# 2_MicroController.net
KiCad netlist of a schematic drawn in Altium Designer
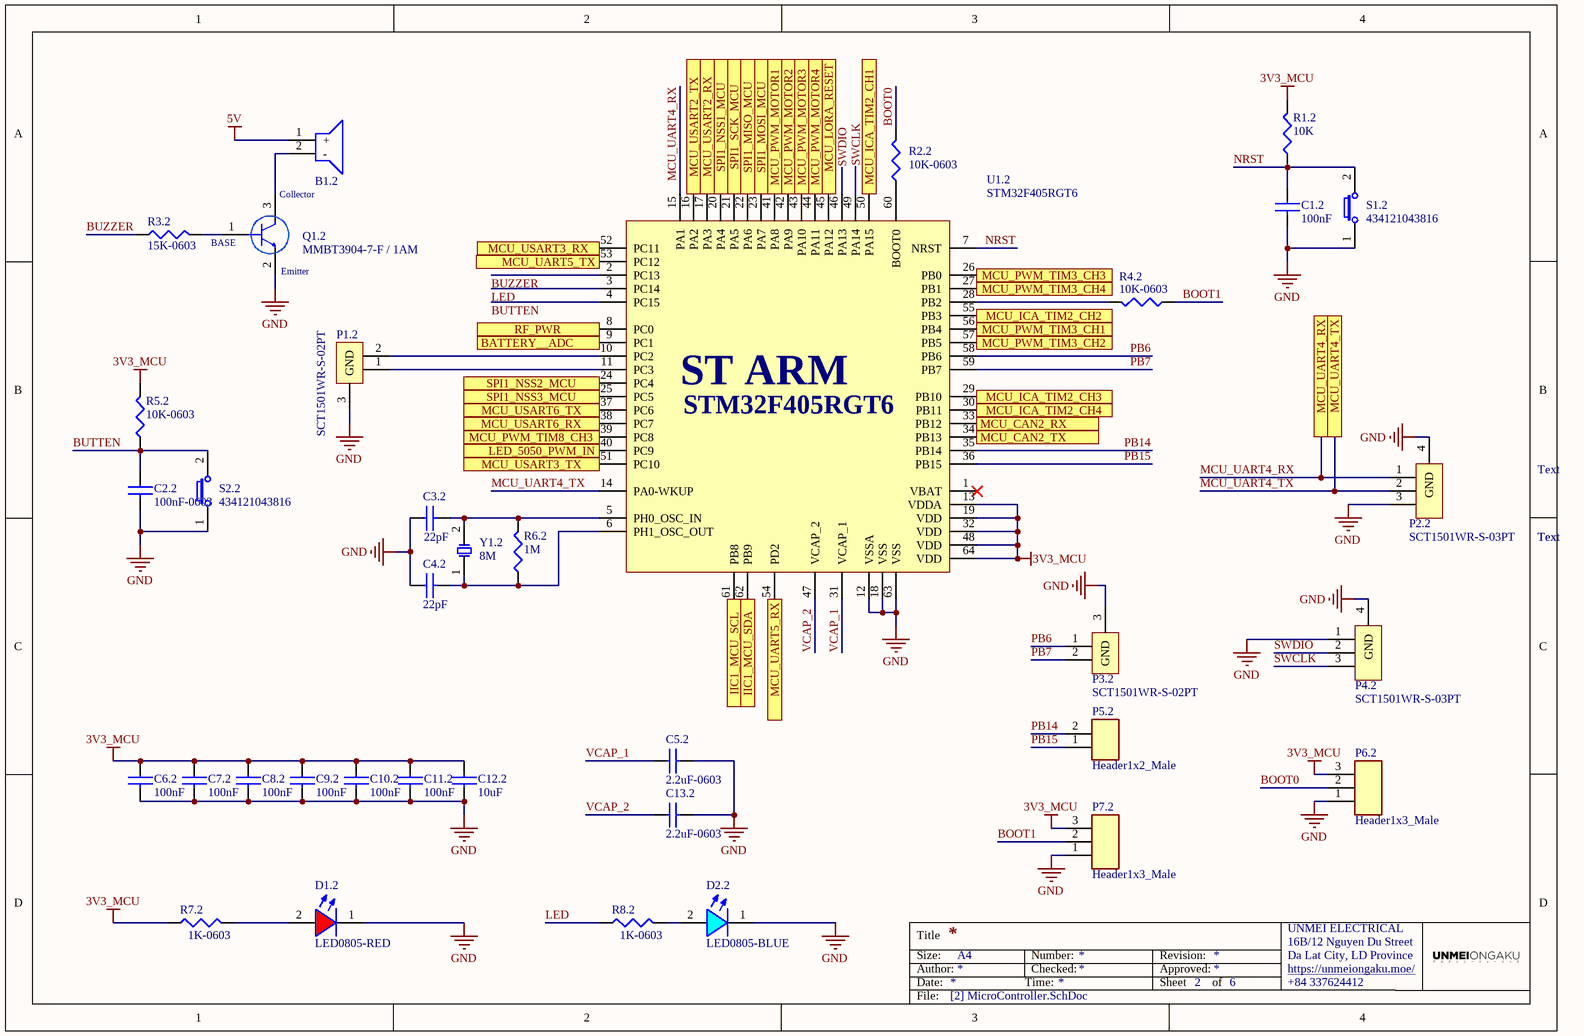
[diagram p0: [2] MicroController.SchDoc]

(export (version "E")
  (design (tool "Eeschema 10.0.6"))
  (components
    (comp (ref "B1.2")
      (value "Buzzer")
      (footprint "Buzzer 9x5mm 60dB")
      (description "9050 DIP Buzzer 9x5mm 60dB")
      (fields (field (name "LOCAL SUPPLIER PART NUMBER") "1209 DIP Buzzer 12x9mm"))
      (libsource (lib "Minh_Lib") (part "Buzzer 9050 - DIP"))
    )
    (comp (ref "C1.2")
      (value "100nF")
      (footprint "CAP0603")
      (description "CAP CER 0.1UF 50V X7R 0603")
      (fields (field (name "TOLERANCE") "±10%"))
      (libsource (lib "Minh_Lib") (part "CC0603KRX7R9BB104"))
    )
    (comp (ref "C2.2")
      (value "100nF-0603")
      (footprint "CAP0603")
      (description "CAP CER 0.1UF 50V X7R 0603")
      (fields (field (name "TOLERANCE") "±10%"))
      (libsource (lib "Minh_Lib") (part "CC0603KRX7R9BB104"))
    )
    (comp (ref "C3.2")
      (value "22pF")
      (footprint "CAP0603")
      (description "Surface Mount Ceramic Multilayer Capacitor 22pF 5% C0G 50V 0603 Paper T/R")
      (fields
        (field (name "MANUFACTURER") "Yageo")
        (field (name "MANUFACTURER PART NUMBER") "CC0603JRNPO9BN220")
      )
      (libsource (lib "Minh_Lib") (part "CC0603JRNPO9BN220"))
    )
    (comp (ref "C4.2")
      (value "22pF")
      (footprint "CAP0603")
      (description "Surface Mount Ceramic Multilayer Capacitor 22pF 5% C0G 50V 0603 Paper T/R")
      (fields
        (field (name "MANUFACTURER") "Yageo")
        (field (name "MANUFACTURER PART NUMBER") "CC0603JRNPO9BN220")
      )
      (libsource (lib "Minh_Lib") (part "CC0603JRNPO9BN220"))
    )
    (comp (ref "C5.2")
      (value "2.2uF-0603")
      (footprint "CAP0603")
      (description "CAP CER 2.2UF 10V X7R 0603")
      (fields (field (name "TOLERANCE") "±10%"))
      (libsource (lib "Minh_Lib") (part "CC0603KRX7R6BB225"))
    )
    (comp (ref "C6.2")
      (value "100nF")
      (footprint "CAP0603")
      (description "CAP CER 0.1UF 50V X7R 0603")
      (fields (field (name "TOLERANCE") "±10%"))
      (libsource (lib "Minh_Lib") (part "CC0603KRX7R9BB104"))
    )
    (comp (ref "C7.2")
      (value "100nF")
      (footprint "CAP0603")
      (description "CAP CER 0.1UF 50V X7R 0603")
      (fields (field (name "TOLERANCE") "±10%"))
      (libsource (lib "Minh_Lib") (part "CC0603KRX7R9BB104"))
    )
    (comp (ref "C8.2")
      (value "100nF")
      (footprint "CAP0603")
      (description "CAP CER 0.1UF 50V X7R 0603")
      (fields (field (name "TOLERANCE") "±10%"))
      (libsource (lib "Minh_Lib") (part "CC0603KRX7R9BB104"))
    )
    (comp (ref "C9.2")
      (value "100nF")
      (footprint "CAP0603")
      (description "CAP CER 0.1UF 50V X7R 0603")
      (fields (field (name "TOLERANCE") "±10%"))
      (libsource (lib "Minh_Lib") (part "CC0603KRX7R9BB104"))
    )
    (comp (ref "C10.2")
      (value "100nF")
      (footprint "CAP0603")
      (description "CAP CER 0.1UF 50V X7R 0603")
      (fields (field (name "TOLERANCE") "±10%"))
      (libsource (lib "Minh_Lib") (part "CC0603KRX7R9BB104"))
    )
    (comp (ref "C11.2")
      (value "100nF")
      (footprint "CAP0603")
      (description "CAP CER 0.1UF 50V X7R 0603")
      (fields (field (name "TOLERANCE") "±10%"))
      (libsource (lib "Minh_Lib") (part "CC0603KRX7R9BB104"))
    )
    (comp (ref "C12.2")
      (value "10uF")
      (footprint "CAP0603")
      (description "CAP CER 10UF 10V X5R 0603")
      (fields (field (name "TOLERANCE") "±10%"))
      (libsource (lib "Minh_Lib") (part "CC0603KRX5R6BB106"))
    )
    (comp (ref "C13.2")
      (value "2.2uF-0603")
      (footprint "CAP0603")
      (description "CAP CER 2.2UF 10V X7R 0603")
      (fields (field (name "TOLERANCE") "±10%"))
      (libsource (lib "Minh_Lib") (part "CC0603KRX7R6BB225"))
    )
    (comp (ref "D1.2")
      (value "LED0805-RED")
      (footprint "LED0805-RED")
      (libsource (lib "Minh_Lib") (part "LED0805-RED"))
    )
    (comp (ref "D2.2")
      (value "LED0805-BLUE")
      (footprint "LED0805-BLUE")
      (libsource (lib "Minh_Lib") (part "LED0805-BLUE"))
    )
    (comp (ref "P1.2")
      (value "SCT1501WR-S-02PT")
      (footprint "Connector ZH1.5 2P SMD")
      (libsource (lib "Minh_Lib") (part "SCT1501WR-S-02PT"))
    )
    (comp (ref "P2.2")
      (value "SCT1501WR-S-03PT")
      (footprint "Connector ZH1.5 3P SMD")
      (libsource (lib "Minh_Lib") (part "SCT1501WR-S-03PT"))
    )
    (comp (ref "P3.2")
      (value "SCT1501WR-S-02PT")
      (footprint "Connector ZH1.5 2P SMD")
      (libsource (lib "") (part "SCT1501WR-S-02PT_1"))
    )
    (comp (ref "P4.2")
      (value "SCT1501WR-S-03PT")
      (footprint "Connector ZH1.5 3P SMD")
      (libsource (lib "Minh_Lib") (part "SCT1501WR-S-03PT"))
    )
    (comp (ref "P5.2")
      (value "Header1x2_Male")
      (footprint "Minh_Lib:HDR1x2_2.54_MALE")
      (description "Header1x2_2.54_MALE")
      (libsource (lib "Minh_Lib") (part "HDR1x2_2.54_MALE"))
    )
    (comp (ref "P6.2")
      (value "Header1x3_Male")
      (footprint "Minh_Lib:HDR1x3_2.54_MALE")
      (description "Header1x3_2.54_MALE")
      (libsource (lib "Minh_Lib") (part "HDR1x3_2.54_MALE"))
    )
    (comp (ref "P7.2")
      (value "Header1x3_Male")
      (footprint "Minh_Lib:HDR1x3_2.54_MALE")
      (description "Header1x3_2.54_MALE")
      (libsource (lib "Minh_Lib") (part "HDR1x3_2.54_MALE"))
    )
    (comp (ref "Q1.2")
      (value "MMBT3904-7-F / 1AM")
      (footprint "SOT23")
      (description "Transistor General Purpose BJT NPN 40 Volt 0.2A Automotive 3-Pin SOT-23")
      (fields
        (field (name "MANUFACTURER") "Diodes Zetex")
        (field (name "MANUFACTURER PART NUMBER") "MMBT3904-7-F")
      )
      (libsource (lib "Minh_Lib") (part "MMBT3904-7-F / 1AM"))
    )
    (comp (ref "R1.2")
      (value "10K")
      (footprint "RES0603 - 3D")
      (description "RES SMD 10K OHM 1% 1/10W 0603")
      (fields
        (field (name "MANUFACTURER") "Yageo")
        (field (name "MANUFACTURER PART NUMBER") "RC0603FR-0710KL")
      )
      (libsource (lib "Minh_Lib") (part "RC0603FR-0710KL"))
    )
    (comp (ref "R2.2")
      (value "10K-0603")
      (footprint "RES0603 - 3D")
      (description "RES SMD 10K OHM 1% 1/10W 0603")
      (fields
        (field (name "MANUFACTURER") "Yageo")
        (field (name "MANUFACTURER PART NUMBER") "RC0603FR-0710KL")
      )
      (libsource (lib "Minh_Lib") (part "RC0603FR-0710KL"))
    )
    (comp (ref "R3.2")
      (value "15K-0603")
      (footprint "RES0603 - 3D")
      (description "Thick Film Resistors - SMD 15K OHM 5%")
      (fields
        (field (name "MANUFACTURER") "Yageo")
        (field (name "MANUFACTURER PART NUMBER") "RC0603JR-0715KL")
      )
      (libsource (lib "Minh_Lib") (part "RC0603JR-0715KL"))
    )
    (comp (ref "R4.2")
      (value "10K-0603")
      (footprint "RES0603 - 3D")
      (description "RES SMD 10K OHM 1% 1/10W 0603")
      (fields
        (field (name "MANUFACTURER") "Yageo")
        (field (name "MANUFACTURER PART NUMBER") "RC0603FR-0710KL")
      )
      (libsource (lib "Minh_Lib") (part "RC0603FR-0710KL"))
    )
    (comp (ref "R5.2")
      (value "10K-0603")
      (footprint "RES0603 - 3D")
      (description "RES SMD 10K OHM 1% 1/10W 0603")
      (fields
        (field (name "MANUFACTURER") "Yageo")
        (field (name "MANUFACTURER PART NUMBER") "RC0603FR-0710KL")
      )
      (libsource (lib "Minh_Lib") (part "RC0603FR-0710KL"))
    )
    (comp (ref "R6.2")
      (value "1M")
      (footprint "RES0603 - 3D")
      (description "RES SMD 1M OHM 5% 1/10W 0603")
      (fields (field (name "TOLERANCE") "±5%"))
      (libsource (lib "Minh_Lib") (part "RC0603JR-071ML"))
    )
    (comp (ref "R7.2")
      (value "1K-0603")
      (footprint "RES0603 - 3D")
      (description "RES SMD 1K OHM 5% 1/10W 0603")
      (fields (field (name "TOLERANCE") "±5%"))
      (libsource (lib "Minh_Lib") (part "RC0603JR-071KL"))
    )
    (comp (ref "R8.2")
      (value "1K-0603")
      (footprint "RES0603 - 3D")
      (description "RES SMD 1K OHM 5% 1/10W 0603")
      (fields (field (name "TOLERANCE") "±5%"))
      (libsource (lib "Minh_Lib") (part "RC0603JR-071KL"))
    )
    (comp (ref "S1.2")
      (value "434121043816")
      (footprint "Switches-6x3.5x4.3mm")
      (description "Switch Tactile Spst-no 0.05A 12V")
      (fields (field (name "MANUFACTURER") "Wurth Electronics"))
      (libsource (lib "Minh_Lib") (part "434121043816"))
    )
    (comp (ref "S2.2")
      (value "434121043816")
      (footprint "Switches-6x3.5x4.3mm")
      (description "Switch Tactile Spst-no 0.05A 12V")
      (fields (field (name "MANUFACTURER") "Wurth Electronics"))
      (libsource (lib "Minh_Lib") (part "434121043816"))
    )
    (comp (ref "U1.2")
      (value "STM32F405RGT6")
      (footprint "LQFP64")
      (description "IC MCU 32BIT 1MB FLASH 64LQFP")
      (fields (field (name "MANUFACTURER") "STMicroelectronics"))
      (libsource (lib "Minh_Lib") (part "STM32F405RGT6"))
    )
    (comp (ref "Y1.2")
      (value "8M")
      (footprint "HC49-S")
      (description "Crystals LO-PRO 8MHz")
      (fields
        (field (name "MANUFACTURER") "Fox Electronics")
        (field (name "MANUFACTURER PART NUMBER") "HC49SSDLF-8.00MHz")
      )
      (libsource (lib "Minh_Lib") (part "Crystals - HC49SSDLF-8.00MHz"))
    )
  )
  (nets
    (net (code "1") (name "/BATTERY__ADC") (class "Default")
      (node (ref "U1.2") (pin "9") (pinfunction "PC1_9") (pintype "passive"))
    )
    (net (code "2") (name "/BOOT0") (class "Default")
      (node (ref "P6.2") (pin "2") (pinfunction "2_2") (pintype "passive"))
      (node (ref "R2.2") (pin "2") (pinfunction "2_2") (pintype "passive"))
    )
    (net (code "3") (name "/BOOT1") (class "Default")
      (node (ref "P7.2") (pin "2") (pinfunction "2_2") (pintype "passive"))
      (node (ref "R4.2") (pin "1") (pinfunction "1_1") (pintype "passive"))
    )
    (net (code "4") (name "/BUTTEN") (class "Default")
      (node (ref "C2.2") (pin "1") (pinfunction "1_1") (pintype "passive"))
      (node (ref "R5.2") (pin "1") (pinfunction "1_1") (pintype "passive"))
      (node (ref "S2.2") (pin "2") (pinfunction "2_2") (pintype "passive"))
      (node (ref "U1.2") (pin "4") (pinfunction "PC15_4") (pintype "passive"))
    )
    (net (code "5") (name "/BUZZER") (class "Default")
      (node (ref "R3.2") (pin "1") (pinfunction "1_1") (pintype "passive"))
      (node (ref "U1.2") (pin "2") (pinfunction "PC13_2") (pintype "passive"))
    )
    (net (code "6") (name "/IIC1_MCU_SCL") (class "Default")
      (node (ref "U1.2") (pin "61") (pinfunction "PB8_61") (pintype "passive"))
    )
    (net (code "7") (name "/IIC1_MCU_SDA") (class "Default")
      (node (ref "U1.2") (pin "62") (pinfunction "PB9_62") (pintype "passive"))
    )
    (net (code "8") (name "/LED") (class "Default")
      (node (ref "R8.2") (pin "1") (pinfunction "1_1") (pintype "passive"))
      (node (ref "U1.2") (pin "3") (pinfunction "PC14_3") (pintype "passive"))
    )
    (net (code "9") (name "/LED_5050_PWM_IN") (class "Default")
      (node (ref "U1.2") (pin "40") (pinfunction "PC9_40") (pintype "passive"))
    )
    (net (code "25") (name "/MCU_PWM_TIM8_CH3") (class "Default")
      (node (ref "U1.2") (pin "39") (pinfunction "PC8_39") (pintype "passive"))
    )
    (net (code "26") (name "/MCU_UART4_RX") (class "Default")
      (node (ref "P2.2") (pin "1") (pinfunction "1_1") (pintype "passive"))
      (node (ref "U1.2") (pin "15") (pinfunction "PA1_15") (pintype "passive"))
    )
    (net (code "27") (name "/MCU_UART4_TX") (class "Default")
      (node (ref "P2.2") (pin "2") (pinfunction "2_2") (pintype "passive"))
      (node (ref "U1.2") (pin "14") (pinfunction "PA0-WKUP_14") (pintype "passive"))
    )
    (net (code "28") (name "/MCU_UART5_RX") (class "Default")
      (node (ref "U1.2") (pin "54") (pinfunction "PD2_54") (pintype "passive"))
    )
    (net (code "29") (name "/MCU_UART5_TX") (class "Default")
      (node (ref "U1.2") (pin "53") (pinfunction "PC12_53") (pintype "passive"))
    )
    (net (code "32") (name "/MCU_USART3_RX") (class "Default")
      (node (ref "U1.2") (pin "52") (pinfunction "PC11_52") (pintype "passive"))
    )
    (net (code "33") (name "/MCU_USART3_TX") (class "Default")
      (node (ref "U1.2") (pin "51") (pinfunction "PC10_51") (pintype "passive"))
    )
    (net (code "34") (name "/MCU_USART6_RX") (class "Default")
      (node (ref "U1.2") (pin "38") (pinfunction "PC7_38") (pintype "passive"))
    )
    (net (code "35") (name "/MCU_USART6_TX") (class "Default")
      (node (ref "U1.2") (pin "37") (pinfunction "PC6_37") (pintype "passive"))
    )
    (net (code "36") (name "/NRST") (class "Default")
      (node (ref "C1.2") (pin "1") (pinfunction "1_1") (pintype "passive"))
      (node (ref "R1.2") (pin "1") (pinfunction "1_1") (pintype "passive"))
      (node (ref "S1.2") (pin "2") (pinfunction "2_2") (pintype "passive"))
      (node (ref "U1.2") (pin "7") (pinfunction "NRST_7") (pintype "passive"))
    )
    (net (code "37") (name "/PB6") (class "Default")
      (node (ref "P3.2") (pin "1") (pinfunction "1_1") (pintype "passive"))
      (node (ref "U1.2") (pin "58") (pinfunction "PB6_58") (pintype "passive"))
    )
    (net (code "38") (name "/PB7") (class "Default")
      (node (ref "P3.2") (pin "2") (pinfunction "2_2") (pintype "passive"))
      (node (ref "U1.2") (pin "59") (pinfunction "PB7_59") (pintype "passive"))
    )
    (net (code "39") (name "/PB14") (class "Default")
      (node (ref "P5.2") (pin "2") (pinfunction "2_2") (pintype "passive"))
      (node (ref "U1.2") (pin "35") (pinfunction "PB14_35") (pintype "passive"))
    )
    (net (code "40") (name "/PB15") (class "Default")
      (node (ref "P5.2") (pin "1") (pinfunction "1_1") (pintype "passive"))
      (node (ref "U1.2") (pin "36") (pinfunction "PB15_36") (pintype "passive"))
    )
    (net (code "41") (name "/RF_PWR") (class "Default")
      (node (ref "U1.2") (pin "8") (pinfunction "PC0_8") (pintype "passive"))
    )
    (net (code "45") (name "/SPI1_NSS2_MCU") (class "Default")
      (node (ref "U1.2") (pin "24") (pinfunction "PC4_24") (pintype "passive"))
    )
    (net (code "46") (name "/SPI1_NSS3_MCU") (class "Default")
      (node (ref "U1.2") (pin "25") (pinfunction "PC5_25") (pintype "passive"))
    )
    (net (code "48") (name "/SWCLK") (class "Default")
      (node (ref "P4.2") (pin "3") (pinfunction "3_3") (pintype "passive"))
      (node (ref "U1.2") (pin "49") (pinfunction "PA14_49") (pintype "passive"))
    )
    (net (code "49") (name "/SWDIO") (class "Default")
      (node (ref "P4.2") (pin "2") (pinfunction "2_2") (pintype "passive"))
      (node (ref "U1.2") (pin "46") (pinfunction "PA13_46") (pintype "passive"))
    )
    (net (code "50") (name "/VCAP_1") (class "Default")
      (node (ref "C5.2") (pin "1") (pinfunction "1_1") (pintype "passive"))
      (node (ref "U1.2") (pin "31") (pinfunction "VCAP_1_31") (pintype "passive"))
    )
    (net (code "51") (name "/VCAP_2") (class "Default")
      (node (ref "C13.2") (pin "1") (pinfunction "1_1") (pintype "passive"))
      (node (ref "U1.2") (pin "47") (pinfunction "VCAP_2_47") (pintype "passive"))
    )
    (net (code "52") (name "3V3_MCU") (class "Default")
      (node (ref "C10.2") (pin "1") (pinfunction "1_1") (pintype "passive"))
      (node (ref "C11.2") (pin "1") (pinfunction "1_1") (pintype "passive"))
      (node (ref "C12.2") (pin "1") (pinfunction "1_1") (pintype "passive"))
      (node (ref "C6.2") (pin "1") (pinfunction "1_1") (pintype "passive"))
      (node (ref "C7.2") (pin "1") (pinfunction "1_1") (pintype "passive"))
      (node (ref "C8.2") (pin "1") (pinfunction "1_1") (pintype "passive"))
      (node (ref "C9.2") (pin "1") (pinfunction "1_1") (pintype "passive"))
      (node (ref "P6.2") (pin "3") (pinfunction "3_3") (pintype "passive"))
      (node (ref "P7.2") (pin "3") (pinfunction "3_3") (pintype "passive"))
      (node (ref "R1.2") (pin "2") (pinfunction "2_2") (pintype "passive"))
      (node (ref "R5.2") (pin "2") (pinfunction "2_2") (pintype "passive"))
      (node (ref "R7.2") (pin "1") (pinfunction "1_1") (pintype "passive"))
      (node (ref "U1.2") (pin "13") (pinfunction "VDDA_13") (pintype "passive"))
      (node (ref "U1.2") (pin "19") (pinfunction "VDD_19") (pintype "passive"))
      (node (ref "U1.2") (pin "32") (pinfunction "VDD_32") (pintype "passive"))
      (node (ref "U1.2") (pin "48") (pinfunction "VDD_48") (pintype "passive"))
      (node (ref "U1.2") (pin "64") (pinfunction "VDD_64") (pintype "passive"))
    )
    (net (code "53") (name "5V") (class "Default")
      (node (ref "B1.2") (pin "1") (pinfunction "+_1") (pintype "passive"))
    )
    (net (code "54") (name "GND") (class "Default")
      (node (ref "C1.2") (pin "2") (pinfunction "2_2") (pintype "passive"))
      (node (ref "C10.2") (pin "2") (pinfunction "2_2") (pintype "passive"))
      (node (ref "C11.2") (pin "2") (pinfunction "2_2") (pintype "passive"))
      (node (ref "C12.2") (pin "2") (pinfunction "2_2") (pintype "passive"))
      (node (ref "C13.2") (pin "2") (pinfunction "2_2") (pintype "passive"))
      (node (ref "C2.2") (pin "2") (pinfunction "2_2") (pintype "passive"))
      (node (ref "C3.2") (pin "1") (pinfunction "1_1") (pintype "passive"))
      (node (ref "C4.2") (pin "1") (pinfunction "1_1") (pintype "passive"))
      (node (ref "C5.2") (pin "2") (pinfunction "2_2") (pintype "passive"))
      (node (ref "C6.2") (pin "2") (pinfunction "2_2") (pintype "passive"))
      (node (ref "C7.2") (pin "2") (pinfunction "2_2") (pintype "passive"))
      (node (ref "C8.2") (pin "2") (pinfunction "2_2") (pintype "passive"))
      (node (ref "C9.2") (pin "2") (pinfunction "2_2") (pintype "passive"))
      (node (ref "D1.2") (pin "1") (pinfunction "+_1") (pintype "passive"))
      (node (ref "D2.2") (pin "1") (pinfunction "+_1") (pintype "passive"))
      (node (ref "P1.2") (pin "3") (pinfunction "GND_3") (pintype "passive"))
      (node (ref "P2.2") (pin "3") (pinfunction "3_3") (pintype "passive"))
      (node (ref "P2.2") (pin "4") (pinfunction "GND_4") (pintype "passive"))
      (node (ref "P3.2") (pin "3") (pinfunction "GND_3") (pintype "passive"))
      (node (ref "P4.2") (pin "1") (pinfunction "1_1") (pintype "passive"))
      (node (ref "P4.2") (pin "4") (pinfunction "GND_4") (pintype "passive"))
      (node (ref "P6.2") (pin "1") (pinfunction "1_1") (pintype "passive"))
      (node (ref "P7.2") (pin "1") (pinfunction "1_1") (pintype "passive"))
      (node (ref "Q1.2") (pin "2") (pinfunction "2_2") (pintype "passive"))
      (node (ref "S1.2") (pin "1") (pinfunction "1_1") (pintype "passive"))
      (node (ref "S2.2") (pin "1") (pinfunction "1_1") (pintype "passive"))
      (node (ref "U1.2") (pin "12") (pinfunction "VSSA_12") (pintype "passive"))
      (node (ref "U1.2") (pin "18") (pinfunction "VSS_18") (pintype "passive"))
      (node (ref "U1.2") (pin "63") (pinfunction "VSS_63") (pintype "passive"))
    )
    (net (code "55") (name "Net-(B1.2--)") (class "Default")
      (node (ref "B1.2") (pin "2") (pinfunction "-_2") (pintype "passive"))
      (node (ref "Q1.2") (pin "3") (pinfunction "3_3") (pintype "passive"))
    )
    (net (code "56") (name "Net-(D1.2-+-Pad2)") (class "Default")
      (node (ref "D1.2") (pin "2") (pinfunction "+_2") (pintype "passive"))
      (node (ref "R7.2") (pin "2") (pinfunction "2_2") (pintype "passive"))
    )
    (net (code "57") (name "Net-(D2.2-+-Pad2)") (class "Default")
      (node (ref "D2.2") (pin "2") (pinfunction "+_2") (pintype "passive"))
      (node (ref "R8.2") (pin "2") (pinfunction "2_2") (pintype "passive"))
    )
    (net (code "58") (name "Net-(Q1.2-Pad1)") (class "Default")
      (node (ref "Q1.2") (pin "1") (pinfunction "1_1") (pintype "passive"))
      (node (ref "R3.2") (pin "2") (pinfunction "2_2") (pintype "passive"))
    )
    (net (code "59") (name "Net-(U1.2-BOOT0)") (class "Default")
      (node (ref "R2.2") (pin "1") (pinfunction "1_1") (pintype "passive"))
      (node (ref "U1.2") (pin "60") (pinfunction "BOOT0_60") (pintype "passive"))
    )
    (net (code "60") (name "Net-(U1.2-PB2)") (class "Default")
      (node (ref "R4.2") (pin "2") (pinfunction "2_2") (pintype "passive"))
      (node (ref "U1.2") (pin "28") (pinfunction "PB2_28") (pintype "passive"))
    )
    (net (code "61") (name "Net-(U1.2-PC2)") (class "Default")
      (node (ref "P1.2") (pin "2") (pinfunction "2_2") (pintype "passive"))
      (node (ref "U1.2") (pin "10") (pinfunction "PC2_10") (pintype "passive"))
    )
    (net (code "62") (name "Net-(U1.2-PC3)") (class "Default")
      (node (ref "P1.2") (pin "1") (pinfunction "1_1") (pintype "passive"))
      (node (ref "U1.2") (pin "11") (pinfunction "PC3_11") (pintype "passive"))
    )
    (net (code "63") (name "Net-(U1.2-PH0_OSC_IN)") (class "Default")
      (node (ref "C3.2") (pin "2") (pinfunction "2_2") (pintype "passive"))
      (node (ref "R6.2") (pin "2") (pinfunction "2_2") (pintype "passive"))
      (node (ref "U1.2") (pin "5") (pinfunction "PH0_OSC_IN_5") (pintype "passive"))
      (node (ref "Y1.2") (pin "2") (pinfunction "7_2") (pintype "passive"))
    )
    (net (code "64") (name "Net-(U1.2-PH1_OSC_OUT)") (class "Default")
      (node (ref "C4.2") (pin "2") (pinfunction "2_2") (pintype "passive"))
      (node (ref "R6.2") (pin "1") (pinfunction "1_1") (pintype "passive"))
      (node (ref "U1.2") (pin "6") (pinfunction "PH1_OSC_OUT_6") (pintype "passive"))
      (node (ref "Y1.2") (pin "1") (pinfunction "6_1") (pintype "passive"))
    )
    (net (code "65") (name "unconnected-(U1.2-PA2-Pad16)") (class "Default")
      (node (ref "U1.2") (pin "16") (pinfunction "PA2_16") (pintype "passive"))
    )
    (net (code "66") (name "unconnected-(U1.2-PA3-Pad17)") (class "Default")
      (node (ref "U1.2") (pin "17") (pinfunction "PA3_17") (pintype "passive"))
    )
    (net (code "67") (name "unconnected-(U1.2-PA4-Pad20)") (class "Default")
      (node (ref "U1.2") (pin "20") (pinfunction "PA4_20") (pintype "passive"))
    )
    (net (code "68") (name "unconnected-(U1.2-PA5-Pad21)") (class "Default")
      (node (ref "U1.2") (pin "21") (pinfunction "PA5_21") (pintype "passive"))
    )
    (net (code "69") (name "unconnected-(U1.2-PA6-Pad22)") (class "Default")
      (node (ref "U1.2") (pin "22") (pinfunction "PA6_22") (pintype "passive"))
    )
    (net (code "70") (name "unconnected-(U1.2-PA7-Pad23)") (class "Default")
      (node (ref "U1.2") (pin "23") (pinfunction "PA7_23") (pintype "passive"))
    )
    (net (code "71") (name "unconnected-(U1.2-PA8-Pad41)") (class "Default")
      (node (ref "U1.2") (pin "41") (pinfunction "PA8_41") (pintype "passive"))
    )
    (net (code "72") (name "unconnected-(U1.2-PA9-Pad42)") (class "Default")
      (node (ref "U1.2") (pin "42") (pinfunction "PA9_42") (pintype "passive"))
    )
    (net (code "73") (name "unconnected-(U1.2-PA10-Pad43)") (class "Default")
      (node (ref "U1.2") (pin "43") (pinfunction "PA10_43") (pintype "passive"))
    )
    (net (code "74") (name "unconnected-(U1.2-PA11-Pad44)") (class "Default")
      (node (ref "U1.2") (pin "44") (pinfunction "PA11_44") (pintype "passive"))
    )
    (net (code "75") (name "unconnected-(U1.2-PA12-Pad45)") (class "Default")
      (node (ref "U1.2") (pin "45") (pinfunction "PA12_45") (pintype "passive"))
    )
    (net (code "76") (name "unconnected-(U1.2-PA15-Pad50)") (class "Default")
      (node (ref "U1.2") (pin "50") (pinfunction "PA15_50") (pintype "passive"))
    )
    (net (code "77") (name "unconnected-(U1.2-PB0-Pad26)") (class "Default")
      (node (ref "U1.2") (pin "26") (pinfunction "PB0_26") (pintype "passive"))
    )
    (net (code "78") (name "unconnected-(U1.2-PB1-Pad27)") (class "Default")
      (node (ref "U1.2") (pin "27") (pinfunction "PB1_27") (pintype "passive"))
    )
    (net (code "79") (name "unconnected-(U1.2-PB3-Pad55)") (class "Default")
      (node (ref "U1.2") (pin "55") (pinfunction "PB3_55") (pintype "passive"))
    )
    (net (code "80") (name "unconnected-(U1.2-PB4-Pad56)") (class "Default")
      (node (ref "U1.2") (pin "56") (pinfunction "PB4_56") (pintype "passive"))
    )
    (net (code "81") (name "unconnected-(U1.2-PB5-Pad57)") (class "Default")
      (node (ref "U1.2") (pin "57") (pinfunction "PB5_57") (pintype "passive"))
    )
    (net (code "82") (name "unconnected-(U1.2-PB10-Pad29)") (class "Default")
      (node (ref "U1.2") (pin "29") (pinfunction "PB10_29") (pintype "passive"))
    )
    (net (code "83") (name "unconnected-(U1.2-PB11-Pad30)") (class "Default")
      (node (ref "U1.2") (pin "30") (pinfunction "PB11_30") (pintype "passive"))
    )
    (net (code "84") (name "unconnected-(U1.2-PB12-Pad33)") (class "Default")
      (node (ref "U1.2") (pin "33") (pinfunction "PB12_33") (pintype "passive"))
    )
    (net (code "85") (name "unconnected-(U1.2-PB13-Pad34)") (class "Default")
      (node (ref "U1.2") (pin "34") (pinfunction "PB13_34") (pintype "passive"))
    )
    (net (code "86") (name "unconnected-(U1.2-VBAT-Pad1)") (class "Default")
      (node (ref "U1.2") (pin "1") (pinfunction "VBAT_1") (pintype "passive+no_connect"))
    )
  )
)
